# SCH_LaserTag-TTGO_2024-07-18.net
KiCad netlist of a schematic drawn in EasyEDA
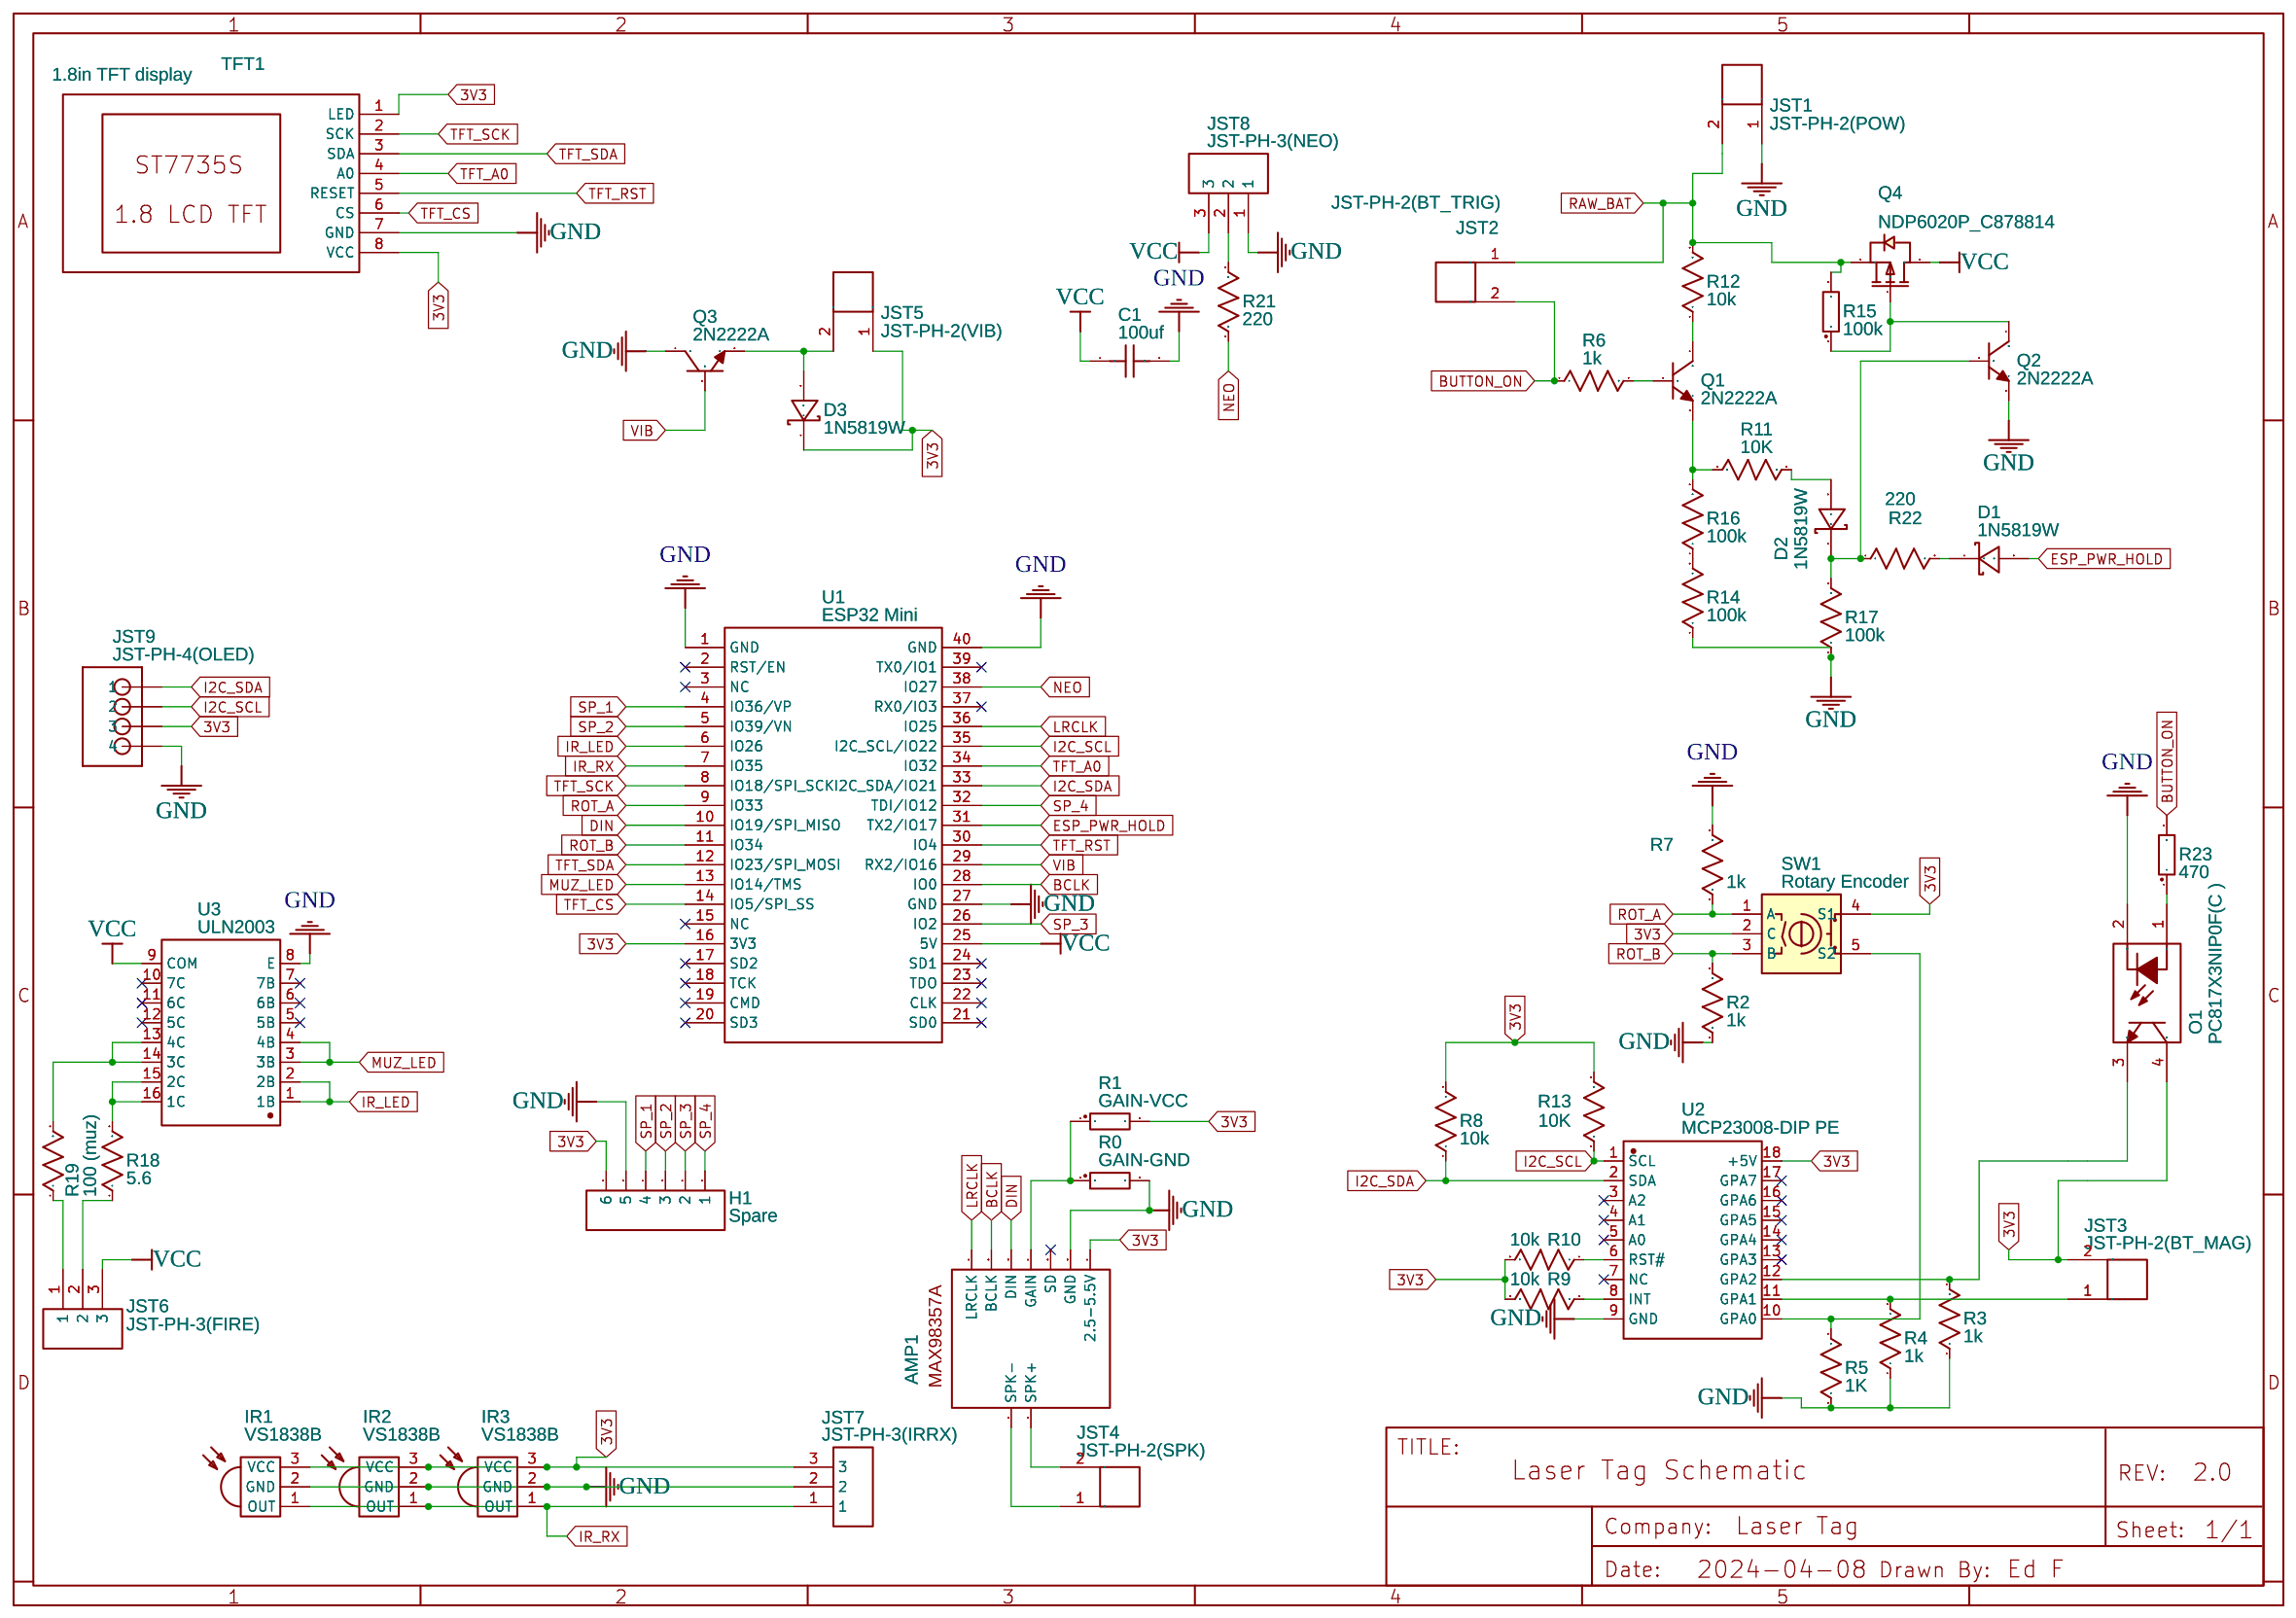
[diagram p0: schematic sheet]

(export (version "E")
  (design (tool "Eeschema 10.0.6"))
  (components
    (comp (ref "AMP1")
      (value "Amplifier")
      (fields (field (name "Manufacturer Part") "3006") (field (name "Manufacturer") "Adafruit"))
      (libsource (lib "") (part "I2S MAX98357A MODULE"))
    )
    (comp (ref "C1") (value "100uf") (libsource (lib "") (part "C_0603_US")))
    (comp (ref "D1")
      (value "1N5819W")
      (fields (field (name "Manufacturer") "Shandong Jingdao Microelectronics"))
      (libsource (lib "") (part "1N5819W_1"))
    )
    (comp (ref "D2")
      (value "1N5819W")
      (fields (field (name "Manufacturer") "Shandong Jingdao Microelectronics"))
      (libsource (lib "") (part "1N5819W"))
    )
    (comp (ref "D3")
      (value "1N5819W")
      (fields (field (name "Manufacturer") "Shandong Jingdao Microelectronics"))
      (libsource (lib "") (part "1N5819W"))
    )
    (comp (ref "H1") (value "Spare") (libsource (lib "") (part "HDR-F-2.54_1x6")))
    (comp (ref "IR1") (value "VS1838B") (libsource (lib "") (part "VS1838B")))
    (comp (ref "IR2") (value "VS1838B") (libsource (lib "") (part "VS1838B")))
    (comp (ref "IR3") (value "VS1838B") (libsource (lib "") (part "VS1838B")))
    (comp (ref "JST1")
      (value "JST-PH-2(POW)")
      (fields (field (name "Manufacturer Part") "JST PH 2 Pin"))
      (libsource (lib "") (part "JST PH 2 Pin_1"))
    )
    (comp (ref "JST2")
      (value "JST-PH-2(BT_TRIG)")
      (fields (field (name "Manufacturer Part") "JST PH 2 Pin"))
      (libsource (lib "") (part "JST PH 2 Pin"))
    )
    (comp (ref "JST3")
      (value "JST-PH-2(BT_MAG)")
      (fields (field (name "Manufacturer Part") "JST PH 2 Pin"))
      (libsource (lib "") (part "JST PH 2 Pin_2"))
    )
    (comp (ref "JST4")
      (value "JST-PH-2(SPK)")
      (fields (field (name "Manufacturer Part") "JST PH 2 Pin"))
      (libsource (lib "") (part "JST PH 2 Pin_2"))
    )
    (comp (ref "JST5")
      (value "JST-PH-2(VIB)")
      (fields (field (name "Manufacturer Part") "JST PH 2 Pin"))
      (libsource (lib "") (part "JST PH 2 Pin_1"))
    )
    (comp (ref "JST6")
      (value "JST-PH-3(FIRE)")
      (fields (field (name "Manufacturer Part") "JST PH 2-PIN 2.0MM TOP ENTRY"))
      (libsource (lib "") (part "JST PH 3-PIN 2.0MM TOP ENTRY_2"))
    )
    (comp (ref "JST7")
      (value "JST-PH-3(IRRX)")
      (fields (field (name "Manufacturer Part") "JST PH 2-PIN 2.0MM TOP ENTRY"))
      (libsource (lib "") (part "JST PH 3-PIN 2.0MM TOP ENTRY"))
    )
    (comp (ref "JST8")
      (value "JST-PH-3(NEO)")
      (fields (field (name "Manufacturer Part") "JST PH 2-PIN 2.0MM TOP ENTRY"))
      (libsource (lib "") (part "JST PH 3-PIN 2.0MM TOP ENTRY_1"))
    )
    (comp (ref "JST9") (value "JST-PH-4(OLED)") (libsource (lib "") (part "JST-PH-4-HEADER")))
    (comp (ref "O1")
      (value "PC817X3NIP0F(C )")
      (fields (field (name "Manufacturer Part") "PC817X3NIP0F") (field (name "Manufacturer") "SHARP(夏普)"))
      (libsource (lib "") (part "PC817X3NIP0F(C )"))
    )
    (comp (ref "Q1")
      (value "2N2222A")
      (fields (field (name "Manufacturer") "BLUE ROCKET(蓝箭)"))
      (libsource (lib "") (part "2N2222A_1"))
    )
    (comp (ref "Q2")
      (value "2N2222A")
      (fields (field (name "Manufacturer") "BLUE ROCKET(蓝箭)"))
      (libsource (lib "") (part "2N2222A_1"))
    )
    (comp (ref "Q3")
      (value "2N2222A")
      (fields (field (name "Manufacturer") "BLUE ROCKET(蓝箭)"))
      (libsource (lib "") (part "2N2222A"))
    )
    (comp (ref "Q4")
      (value "NDP6020P_C878814")
      (fields (field (name "Manufacturer Part") "NDP6020P-VB") (field (name "Manufacturer") "VBsemi(微碧半导体)"))
      (libsource (lib "") (part "NDP6020P_C878814"))
    )
    (comp (ref "R0") (value "GAIN-GND") (libsource (lib "") (part "PTH-RESISTOR-VERT-1W_1")))
    (comp (ref "R1") (value "GAIN-VCC") (libsource (lib "") (part "PTH-RESISTOR-VERT-1W_1")))
    (comp (ref "R2") (value "1k") (libsource (lib "") (part "R_0603_US")))
    (comp (ref "R3") (value "1k") (libsource (lib "") (part "R_0603_US")))
    (comp (ref "R4") (value "1k") (libsource (lib "") (part "R_0603_US")))
    (comp (ref "R5") (value "1K") (libsource (lib "") (part "R_0603_US")))
    (comp (ref "R6") (value "1k") (libsource (lib "") (part "R_0603_US_1")))
    (comp (ref "R7") (value "1k") (libsource (lib "") (part "R_0603_US")))
    (comp (ref "R8") (value "10k") (libsource (lib "") (part "R_0603_US")))
    (comp (ref "R9") (value "10k") (libsource (lib "") (part "R_0603_US_2")))
    (comp (ref "R10") (value "10k") (libsource (lib "") (part "R_0603_US_2")))
    (comp (ref "R11") (value "10K") (libsource (lib "") (part "R_0603_US_1")))
    (comp (ref "R12") (value "10k") (libsource (lib "") (part "R_0603_US")))
    (comp (ref "R13") (value "10K") (libsource (lib "") (part "R_0603_US")))
    (comp (ref "R14") (value "100k") (libsource (lib "") (part "R_0603_US")))
    (comp (ref "R15") (value "100k") (libsource (lib "") (part "PTH-RESISTOR-VERT-1W")))
    (comp (ref "R16") (value "100k") (libsource (lib "") (part "R_0603_US")))
    (comp (ref "R17") (value "100k") (libsource (lib "") (part "R_0603_US")))
    (comp (ref "R18") (value "5.6") (libsource (lib "") (part "R_0603_US")))
    (comp (ref "R19") (value "100 (muz)") (libsource (lib "") (part "R_0603_US")))
    (comp (ref "R21") (value "220") (libsource (lib "") (part "R_0603_US")))
    (comp (ref "R22") (value "220") (libsource (lib "") (part "R_0603_US_1")))
    (comp (ref "R23") (value "470") (libsource (lib "") (part "PTH-RESISTOR-VERT-1W")))
    (comp (ref "SW1") (value "Rotary Encoder") (libsource (lib "") (part "Rotary Encoder")))
    (comp (ref "TFT1")
      (value "1.8in TFT display")
      (libsource (lib "") (part "1.8inch LCD TFT ST7735S Waveshare"))
    )
    (comp (ref "U1") (value "ESP32 Mini") (libsource (lib "") (part "ESP32 Mini")))
    (comp (ref "U2")
      (value "MCP23008-DIP PE")
      (fields
        (field (name "Manufacturer Part") "MCP23008-E/P")
        (field (name "Manufacturer") "MICROCHIP(美国微芯)")
      )
      (libsource (lib "") (part "MCP23008-DIP PE"))
    )
    (comp (ref "U3")
      (value "ULN2003")
      (fields (field (name "Manufacturer Part") "ULN2003APG") (field (name "Manufacturer") "TOSHIBA"))
      (libsource (lib "") (part "ULN2003APG"))
    )
  )
  (nets
    (net (code "1") (name "3V3") (class "Default")
      (node (ref "AMP1") (pin "H7") (pinfunction "2.5-5.5V_H7") (pintype "unspecified"))
      (node (ref "D3") (pin "1") (pinfunction "1_1") (pintype "unspecified"))
      (node (ref "H1") (pin "6") (pinfunction "6_6") (pintype "input"))
      (node (ref "IR1") (pin "3") (pinfunction "VCC_3") (pintype "bidirectional"))
      (node (ref "IR2") (pin "3") (pinfunction "VCC_3") (pintype "bidirectional"))
      (node (ref "IR3") (pin "3") (pinfunction "VCC_3") (pintype "bidirectional"))
      (node (ref "JST3") (pin "2") (pinfunction "2_2") (pintype "unspecified"))
      (node (ref "JST5") (pin "1") (pinfunction "1_1") (pintype "unspecified"))
      (node (ref "JST7") (pin "3") (pinfunction "3_3") (pintype "unspecified"))
      (node (ref "JST9") (pin "3") (pinfunction "3_3") (pintype "unspecified"))
      (node (ref "O1") (pin "4") (pinfunction "COL_4") (pintype "unspecified"))
      (node (ref "R1") (pin "2") (pinfunction "2_2") (pintype "input"))
      (node (ref "R10") (pin "2") (pinfunction "2_2") (pintype "unspecified"))
      (node (ref "R13") (pin "2") (pinfunction "2_2") (pintype "unspecified"))
      (node (ref "R8") (pin "2") (pinfunction "2_2") (pintype "unspecified"))
      (node (ref "R9") (pin "2") (pinfunction "2_2") (pintype "unspecified"))
      (node (ref "SW1") (pin "2") (pinfunction "C_2") (pintype "unspecified"))
      (node (ref "SW1") (pin "4") (pinfunction "S1_4") (pintype "unspecified"))
      (node (ref "TFT1") (pin "1") (pinfunction "LED_1") (pintype "unspecified"))
      (node (ref "TFT1") (pin "8") (pinfunction "VCC_8") (pintype "unspecified"))
      (node (ref "U1") (pin "16") (pinfunction "3V3_16") (pintype "unspecified"))
      (node (ref "U2") (pin "18") (pinfunction "+5V_18") (pintype "unspecified"))
    )
    (net (code "2") (name "BCLK") (class "Default")
      (node (ref "AMP1") (pin "H2") (pinfunction "BCLK_H2") (pintype "unspecified"))
      (node (ref "U1") (pin "28") (pinfunction "IO0_28") (pintype "unspecified"))
    )
    (net (code "3") (name "BUTTON_ON") (class "Default")
      (node (ref "JST2") (pin "2") (pinfunction "2_2") (pintype "unspecified"))
      (node (ref "R23") (pin "2") (pinfunction "2_2") (pintype "input"))
      (node (ref "R6") (pin "1") (pinfunction "1_1") (pintype "unspecified"))
    )
    (net (code "4") (name "DIN") (class "Default")
      (node (ref "AMP1") (pin "H3") (pinfunction "DIN_H3") (pintype "unspecified"))
      (node (ref "U1") (pin "10") (pinfunction "IO19/SPI_MISO_10") (pintype "unspecified"))
    )
    (net (code "5") (name "ESP_PWR_HOLD") (class "Default")
      (node (ref "D1") (pin "2") (pinfunction "2_2") (pintype "unspecified"))
      (node (ref "U1") (pin "31") (pinfunction "TX2/IO17_31") (pintype "unspecified"))
    )
    (net (code "6") (name "GND") (class "Default")
      (node (ref "AMP1") (pin "H6") (pinfunction "GND_H6") (pintype "unspecified"))
      (node (ref "C1") (pin "2") (pinfunction "2_2") (pintype "unspecified"))
      (node (ref "H1") (pin "5") (pinfunction "5_5") (pintype "input"))
      (node (ref "IR1") (pin "2") (pinfunction "GND_2") (pintype "bidirectional"))
      (node (ref "IR2") (pin "2") (pinfunction "GND_2") (pintype "bidirectional"))
      (node (ref "IR3") (pin "2") (pinfunction "GND_2") (pintype "bidirectional"))
      (node (ref "JST1") (pin "1") (pinfunction "1_1") (pintype "unspecified"))
      (node (ref "JST7") (pin "2") (pinfunction "2_2") (pintype "unspecified"))
      (node (ref "JST8") (pin "1") (pinfunction "1_1") (pintype "unspecified"))
      (node (ref "JST9") (pin "4") (pinfunction "4_4") (pintype "unspecified"))
      (node (ref "O1") (pin "2") (pinfunction "CAT_2") (pintype "unspecified"))
      (node (ref "Q2") (pin "3") (pinfunction "E_3") (pintype "unspecified"))
      (node (ref "Q3") (pin "1") (pinfunction "C_1") (pintype "unspecified"))
      (node (ref "R0") (pin "2") (pinfunction "2_2") (pintype "input"))
      (node (ref "R14") (pin "1") (pinfunction "1_1") (pintype "unspecified"))
      (node (ref "R17") (pin "1") (pinfunction "1_1") (pintype "unspecified"))
      (node (ref "R2") (pin "1") (pinfunction "1_1") (pintype "unspecified"))
      (node (ref "R3") (pin "1") (pinfunction "1_1") (pintype "unspecified"))
      (node (ref "R4") (pin "1") (pinfunction "1_1") (pintype "unspecified"))
      (node (ref "R5") (pin "1") (pinfunction "1_1") (pintype "unspecified"))
      (node (ref "R7") (pin "2") (pinfunction "2_2") (pintype "unspecified"))
      (node (ref "TFT1") (pin "7") (pinfunction "GND_7") (pintype "unspecified"))
      (node (ref "U1") (pin "1") (pinfunction "GND_1") (pintype "unspecified"))
      (node (ref "U1") (pin "27") (pinfunction "GND_27") (pintype "unspecified"))
      (node (ref "U1") (pin "40") (pinfunction "GND_40") (pintype "unspecified"))
      (node (ref "U2") (pin "9") (pinfunction "GND_9") (pintype "unspecified"))
      (node (ref "U3") (pin "8") (pinfunction "E_8") (pintype "unspecified"))
    )
    (net (code "7") (name "I2C_SCL") (class "Default")
      (node (ref "JST9") (pin "2") (pinfunction "2_2") (pintype "unspecified"))
      (node (ref "R13") (pin "1") (pinfunction "1_1") (pintype "unspecified"))
      (node (ref "U1") (pin "35") (pinfunction "I2C_SCL/IO22_35") (pintype "unspecified"))
      (node (ref "U2") (pin "1") (pinfunction "SCL_1") (pintype "unspecified"))
    )
    (net (code "8") (name "I2C_SDA") (class "Default")
      (node (ref "JST9") (pin "1") (pinfunction "1_1") (pintype "unspecified"))
      (node (ref "R8") (pin "1") (pinfunction "1_1") (pintype "unspecified"))
      (node (ref "U1") (pin "33") (pinfunction "I2C_SDA/IO21_33") (pintype "unspecified"))
      (node (ref "U2") (pin "2") (pinfunction "SDA_2") (pintype "unspecified"))
    )
    (net (code "9") (name "IR_LED") (class "Default")
      (node (ref "U1") (pin "6") (pinfunction "IO26_6") (pintype "unspecified"))
      (node (ref "U3") (pin "1") (pinfunction "1B_1") (pintype "unspecified"))
      (node (ref "U3") (pin "2") (pinfunction "2B_2") (pintype "unspecified"))
    )
    (net (code "10") (name "IR_RX") (class "Default")
      (node (ref "IR1") (pin "1") (pinfunction "OUT_1") (pintype "bidirectional"))
      (node (ref "IR2") (pin "1") (pinfunction "OUT_1") (pintype "bidirectional"))
      (node (ref "IR3") (pin "1") (pinfunction "OUT_1") (pintype "bidirectional"))
      (node (ref "JST7") (pin "1") (pinfunction "1_1") (pintype "unspecified"))
      (node (ref "U1") (pin "7") (pinfunction "IO35_7") (pintype "unspecified"))
    )
    (net (code "11") (name "LRCLK") (class "Default")
      (node (ref "AMP1") (pin "H1") (pinfunction "LRCLK_H1") (pintype "unspecified"))
      (node (ref "U1") (pin "36") (pinfunction "IO25_36") (pintype "unspecified"))
    )
    (net (code "12") (name "MUZ_LED") (class "Default")
      (node (ref "U1") (pin "13") (pinfunction "IO14/TMS_13") (pintype "unspecified"))
      (node (ref "U3") (pin "3") (pinfunction "3B_3") (pintype "unspecified"))
      (node (ref "U3") (pin "4") (pinfunction "4B_4") (pintype "unspecified"))
    )
    (net (code "13") (name "NEO") (class "Default")
      (node (ref "R21") (pin "1") (pinfunction "1_1") (pintype "unspecified"))
      (node (ref "U1") (pin "38") (pinfunction "IO27_38") (pintype "unspecified"))
    )
    (net (code "14") (name "Net-(AMP1-GAIN)") (class "Default")
      (node (ref "AMP1") (pin "H4") (pinfunction "GAIN_H4") (pintype "unspecified"))
      (node (ref "R0") (pin "1") (pinfunction "1_1") (pintype "input"))
      (node (ref "R1") (pin "1") (pinfunction "1_1") (pintype "input"))
    )
    (net (code "15") (name "Net-(AMP1-SPK+)") (class "Default")
      (node (ref "AMP1") (pin "H9") (pinfunction "SPK+_H9") (pintype "unspecified"))
      (node (ref "JST4") (pin "2") (pinfunction "2_2") (pintype "unspecified"))
    )
    (net (code "16") (name "Net-(AMP1-SPK-)") (class "Default")
      (node (ref "AMP1") (pin "H8") (pinfunction "SPK-_H8") (pintype "unspecified"))
      (node (ref "JST4") (pin "1") (pinfunction "1_1") (pintype "unspecified"))
    )
    (net (code "17") (name "Net-(D1-Pad1)") (class "Default")
      (node (ref "D1") (pin "1") (pinfunction "1_1") (pintype "unspecified"))
      (node (ref "R22") (pin "2") (pinfunction "2_2") (pintype "unspecified"))
    )
    (net (code "18") (name "Net-(D2-Pad2)") (class "Default")
      (node (ref "D2") (pin "2") (pinfunction "2_2") (pintype "unspecified"))
      (node (ref "R11") (pin "2") (pinfunction "2_2") (pintype "unspecified"))
    )
    (net (code "19") (name "Net-(JST6-Pad1)") (class "Default")
      (node (ref "JST6") (pin "1") (pinfunction "1_1") (pintype "unspecified"))
      (node (ref "R19") (pin "1") (pinfunction "1_1") (pintype "unspecified"))
    )
    (net (code "20") (name "Net-(JST6-Pad2)") (class "Default")
      (node (ref "JST6") (pin "2") (pinfunction "2_2") (pintype "unspecified"))
      (node (ref "R18") (pin "1") (pinfunction "1_1") (pintype "unspecified"))
    )
    (net (code "21") (name "Net-(JST8-Pad2)") (class "Default")
      (node (ref "JST8") (pin "2") (pinfunction "2_2") (pintype "unspecified"))
      (node (ref "R21") (pin "2") (pinfunction "2_2") (pintype "unspecified"))
    )
    (net (code "22") (name "Net-(O1-AN)") (class "Default")
      (node (ref "O1") (pin "1") (pinfunction "AN_1") (pintype "unspecified"))
      (node (ref "R23") (pin "1") (pinfunction "1_1") (pintype "input"))
    )
    (net (code "23") (name "Net-(O1-EM)") (class "Default")
      (node (ref "O1") (pin "3") (pinfunction "EM_3") (pintype "unspecified"))
      (node (ref "R3") (pin "2") (pinfunction "2_2") (pintype "unspecified"))
      (node (ref "U2") (pin "12") (pinfunction "GPA2_12") (pintype "unspecified"))
    )
    (net (code "24") (name "Net-(Q1-B)") (class "Default")
      (node (ref "Q1") (pin "2") (pinfunction "B_2") (pintype "unspecified"))
      (node (ref "R6") (pin "2") (pinfunction "2_2") (pintype "unspecified"))
    )
    (net (code "25") (name "Net-(Q1-C)") (class "Default")
      (node (ref "Q1") (pin "1") (pinfunction "C_1") (pintype "unspecified"))
      (node (ref "R12") (pin "1") (pinfunction "1_1") (pintype "unspecified"))
    )
    (net (code "26") (name "Net-(Q1-E)") (class "Default")
      (node (ref "Q1") (pin "3") (pinfunction "E_3") (pintype "unspecified"))
      (node (ref "R11") (pin "1") (pinfunction "1_1") (pintype "unspecified"))
      (node (ref "R16") (pin "2") (pinfunction "2_2") (pintype "unspecified"))
    )
    (net (code "27") (name "Net-(Q2-B)") (class "Default")
      (node (ref "D2") (pin "1") (pinfunction "1_1") (pintype "unspecified"))
      (node (ref "Q2") (pin "2") (pinfunction "B_2") (pintype "unspecified"))
      (node (ref "R17") (pin "2") (pinfunction "2_2") (pintype "unspecified"))
      (node (ref "R22") (pin "1") (pinfunction "1_1") (pintype "unspecified"))
    )
    (net (code "28") (name "Net-(Q2-C)") (class "Default")
      (node (ref "Q2") (pin "1") (pinfunction "C_1") (pintype "unspecified"))
      (node (ref "Q4") (pin "1") (pinfunction "G_1") (pintype "unspecified"))
      (node (ref "R15") (pin "1") (pinfunction "1_1") (pintype "input"))
    )
    (net (code "29") (name "Net-(Q3-E)") (class "Default")
      (node (ref "D3") (pin "2") (pinfunction "2_2") (pintype "unspecified"))
      (node (ref "JST5") (pin "2") (pinfunction "2_2") (pintype "unspecified"))
      (node (ref "Q3") (pin "3") (pinfunction "E_3") (pintype "unspecified"))
    )
    (net (code "30") (name "Net-(R14-Pad2)") (class "Default")
      (node (ref "R14") (pin "2") (pinfunction "2_2") (pintype "unspecified"))
      (node (ref "R16") (pin "1") (pinfunction "1_1") (pintype "unspecified"))
    )
    (net (code "31") (name "Net-(SW1-S2)") (class "Default")
      (node (ref "R5") (pin "2") (pinfunction "2_2") (pintype "unspecified"))
      (node (ref "SW1") (pin "5") (pinfunction "S2_5") (pintype "unspecified"))
      (node (ref "U2") (pin "10") (pinfunction "GPA0_10") (pintype "unspecified"))
    )
    (net (code "32") (name "Net-(U2-GPA1)") (class "Default")
      (node (ref "JST3") (pin "1") (pinfunction "1_1") (pintype "unspecified"))
      (node (ref "R4") (pin "2") (pinfunction "2_2") (pintype "unspecified"))
      (node (ref "U2") (pin "11") (pinfunction "GPA1_11") (pintype "unspecified"))
    )
    (net (code "33") (name "Net-(U2-INT)") (class "Default")
      (node (ref "R9") (pin "1") (pinfunction "1_1") (pintype "unspecified"))
      (node (ref "U2") (pin "8") (pinfunction "INT_8") (pintype "unspecified"))
    )
    (net (code "34") (name "Net-(U2-RST#)") (class "Default")
      (node (ref "R10") (pin "1") (pinfunction "1_1") (pintype "unspecified"))
      (node (ref "U2") (pin "6") (pinfunction "RST#_6") (pintype "unspecified"))
    )
    (net (code "35") (name "Net-(U3-1C)") (class "Default")
      (node (ref "R18") (pin "2") (pinfunction "2_2") (pintype "unspecified"))
      (node (ref "U3") (pin "15") (pinfunction "2C_15") (pintype "unspecified"))
      (node (ref "U3") (pin "16") (pinfunction "1C_16") (pintype "unspecified"))
    )
    (net (code "36") (name "Net-(U3-3C)") (class "Default")
      (node (ref "R19") (pin "2") (pinfunction "2_2") (pintype "unspecified"))
      (node (ref "U3") (pin "13") (pinfunction "4C_13") (pintype "unspecified"))
      (node (ref "U3") (pin "14") (pinfunction "3C_14") (pintype "unspecified"))
    )
    (net (code "37") (name "RAW_BAT") (class "Default")
      (node (ref "JST1") (pin "2") (pinfunction "2_2") (pintype "unspecified"))
      (node (ref "JST2") (pin "1") (pinfunction "1_1") (pintype "unspecified"))
      (node (ref "Q4") (pin "3") (pinfunction "S_3") (pintype "unspecified"))
      (node (ref "R12") (pin "2") (pinfunction "2_2") (pintype "unspecified"))
      (node (ref "R15") (pin "2") (pinfunction "2_2") (pintype "input"))
    )
    (net (code "38") (name "ROT_A") (class "Default")
      (node (ref "R7") (pin "1") (pinfunction "1_1") (pintype "unspecified"))
      (node (ref "SW1") (pin "1") (pinfunction "A_1") (pintype "unspecified"))
      (node (ref "U1") (pin "9") (pinfunction "IO33_9") (pintype "unspecified"))
    )
    (net (code "39") (name "ROT_B") (class "Default")
      (node (ref "R2") (pin "2") (pinfunction "2_2") (pintype "unspecified"))
      (node (ref "SW1") (pin "3") (pinfunction "B_3") (pintype "unspecified"))
      (node (ref "U1") (pin "11") (pinfunction "IO34_11") (pintype "unspecified"))
    )
    (net (code "40") (name "SP_1") (class "Default")
      (node (ref "H1") (pin "4") (pinfunction "4_4") (pintype "input"))
      (node (ref "U1") (pin "4") (pinfunction "IO36/VP_4") (pintype "unspecified"))
    )
    (net (code "41") (name "SP_2") (class "Default")
      (node (ref "H1") (pin "3") (pinfunction "3_3") (pintype "input"))
      (node (ref "U1") (pin "5") (pinfunction "IO39/VN_5") (pintype "unspecified"))
    )
    (net (code "42") (name "SP_3") (class "Default")
      (node (ref "H1") (pin "2") (pinfunction "2_2") (pintype "input"))
      (node (ref "U1") (pin "26") (pinfunction "IO2_26") (pintype "unspecified"))
    )
    (net (code "43") (name "SP_4") (class "Default")
      (node (ref "H1") (pin "1") (pinfunction "1_1") (pintype "input"))
      (node (ref "U1") (pin "32") (pinfunction "TDI/IO12_32") (pintype "unspecified"))
    )
    (net (code "44") (name "TFT_A0") (class "Default")
      (node (ref "TFT1") (pin "4") (pinfunction "A0_4") (pintype "unspecified"))
      (node (ref "U1") (pin "34") (pinfunction "IO32_34") (pintype "unspecified"))
    )
    (net (code "45") (name "TFT_CS") (class "Default")
      (node (ref "TFT1") (pin "6") (pinfunction "CS_6") (pintype "unspecified"))
      (node (ref "U1") (pin "14") (pinfunction "IO5/SPI_SS_14") (pintype "unspecified"))
    )
    (net (code "46") (name "TFT_RST") (class "Default")
      (node (ref "TFT1") (pin "5") (pinfunction "RESET_5") (pintype "unspecified"))
      (node (ref "U1") (pin "30") (pinfunction "IO4_30") (pintype "unspecified"))
    )
    (net (code "47") (name "TFT_SCK") (class "Default")
      (node (ref "TFT1") (pin "2") (pinfunction "SCK_2") (pintype "unspecified"))
      (node (ref "U1") (pin "8") (pinfunction "IO18/SPI_SCK_8") (pintype "unspecified"))
    )
    (net (code "48") (name "TFT_SDA") (class "Default")
      (node (ref "TFT1") (pin "3") (pinfunction "SDA_3") (pintype "unspecified"))
      (node (ref "U1") (pin "12") (pinfunction "IO23/SPI_MOSI_12") (pintype "unspecified"))
    )
    (net (code "49") (name "VCC") (class "Default")
      (node (ref "C1") (pin "1") (pinfunction "1_1") (pintype "unspecified"))
      (node (ref "JST6") (pin "3") (pinfunction "3_3") (pintype "unspecified"))
      (node (ref "JST8") (pin "3") (pinfunction "3_3") (pintype "unspecified"))
      (node (ref "Q4") (pin "2") (pinfunction "D_2") (pintype "unspecified"))
      (node (ref "U1") (pin "25") (pinfunction "5V_25") (pintype "unspecified"))
      (node (ref "U3") (pin "9") (pinfunction "COM_9") (pintype "unspecified"))
    )
    (net (code "50") (name "VIB") (class "Default")
      (node (ref "Q3") (pin "2") (pinfunction "B_2") (pintype "unspecified"))
      (node (ref "U1") (pin "29") (pinfunction "RX2/IO16_29") (pintype "unspecified"))
    )
    (net (code "51") (name "unconnected-(AMP1-SD-PadH5)") (class "Default")
      (node (ref "AMP1") (pin "H5") (pinfunction "SD_H5") (pintype "unspecified+no_connect"))
    )
    (net (code "52") (name "unconnected-(U1-CLK-Pad22)") (class "Default")
      (node (ref "U1") (pin "22") (pinfunction "CLK_22") (pintype "unspecified+no_connect"))
    )
    (net (code "53") (name "unconnected-(U1-CMD-Pad19)") (class "Default")
      (node (ref "U1") (pin "19") (pinfunction "CMD_19") (pintype "unspecified+no_connect"))
    )
    (net (code "54") (name "unconnected-(U1-NC-Pad3)") (class "Default")
      (node (ref "U1") (pin "3") (pinfunction "NC_3") (pintype "unspecified+no_connect"))
    )
    (net (code "55") (name "unconnected-(U1-NC-Pad15)") (class "Default")
      (node (ref "U1") (pin "15") (pinfunction "NC_15") (pintype "unspecified+no_connect"))
    )
    (net (code "56") (name "unconnected-(U1-RST{slash}EN-Pad2)") (class "Default")
      (node (ref "U1") (pin "2") (pinfunction "RST/EN_2") (pintype "unspecified+no_connect"))
    )
    (net (code "57") (name "unconnected-(U1-RX0{slash}IO3-Pad37)") (class "Default")
      (node (ref "U1") (pin "37") (pinfunction "RX0/IO3_37") (pintype "unspecified+no_connect"))
    )
    (net (code "58") (name "unconnected-(U1-SD0-Pad21)") (class "Default")
      (node (ref "U1") (pin "21") (pinfunction "SD0_21") (pintype "unspecified+no_connect"))
    )
    (net (code "59") (name "unconnected-(U1-SD1-Pad24)") (class "Default")
      (node (ref "U1") (pin "24") (pinfunction "SD1_24") (pintype "unspecified+no_connect"))
    )
    (net (code "60") (name "unconnected-(U1-SD2-Pad17)") (class "Default")
      (node (ref "U1") (pin "17") (pinfunction "SD2_17") (pintype "unspecified+no_connect"))
    )
    (net (code "61") (name "unconnected-(U1-SD3-Pad20)") (class "Default")
      (node (ref "U1") (pin "20") (pinfunction "SD3_20") (pintype "unspecified+no_connect"))
    )
    (net (code "62") (name "unconnected-(U1-TCK-Pad18)") (class "Default")
      (node (ref "U1") (pin "18") (pinfunction "TCK_18") (pintype "unspecified+no_connect"))
    )
    (net (code "63") (name "unconnected-(U1-TDO-Pad23)") (class "Default")
      (node (ref "U1") (pin "23") (pinfunction "TDO_23") (pintype "unspecified+no_connect"))
    )
    (net (code "64") (name "unconnected-(U1-TX0{slash}IO1-Pad39)") (class "Default")
      (node (ref "U1") (pin "39") (pinfunction "TX0/IO1_39") (pintype "unspecified+no_connect"))
    )
    (net (code "65") (name "unconnected-(U2-A0-Pad5)") (class "Default")
      (node (ref "U2") (pin "5") (pinfunction "A0_5") (pintype "unspecified+no_connect"))
    )
    (net (code "66") (name "unconnected-(U2-A1-Pad4)") (class "Default")
      (node (ref "U2") (pin "4") (pinfunction "A1_4") (pintype "unspecified+no_connect"))
    )
    (net (code "67") (name "unconnected-(U2-A2-Pad3)") (class "Default")
      (node (ref "U2") (pin "3") (pinfunction "A2_3") (pintype "unspecified+no_connect"))
    )
    (net (code "68") (name "unconnected-(U2-GPA3-Pad13)") (class "Default")
      (node (ref "U2") (pin "13") (pinfunction "GPA3_13") (pintype "unspecified+no_connect"))
    )
    (net (code "69") (name "unconnected-(U2-GPA4-Pad14)") (class "Default")
      (node (ref "U2") (pin "14") (pinfunction "GPA4_14") (pintype "unspecified+no_connect"))
    )
    (net (code "70") (name "unconnected-(U2-GPA5-Pad15)") (class "Default")
      (node (ref "U2") (pin "15") (pinfunction "GPA5_15") (pintype "unspecified+no_connect"))
    )
    (net (code "71") (name "unconnected-(U2-GPA6-Pad16)") (class "Default")
      (node (ref "U2") (pin "16") (pinfunction "GPA6_16") (pintype "unspecified+no_connect"))
    )
    (net (code "72") (name "unconnected-(U2-GPA7-Pad17)") (class "Default")
      (node (ref "U2") (pin "17") (pinfunction "GPA7_17") (pintype "unspecified+no_connect"))
    )
    (net (code "73") (name "unconnected-(U2-NC-Pad7)") (class "Default")
      (node (ref "U2") (pin "7") (pinfunction "NC_7") (pintype "unspecified+no_connect"))
    )
    (net (code "74") (name "unconnected-(U3-5B-Pad5)") (class "Default")
      (node (ref "U3") (pin "5") (pinfunction "5B_5") (pintype "unspecified+no_connect"))
    )
    (net (code "75") (name "unconnected-(U3-5C-Pad12)") (class "Default")
      (node (ref "U3") (pin "12") (pinfunction "5C_12") (pintype "unspecified+no_connect"))
    )
    (net (code "76") (name "unconnected-(U3-6B-Pad6)") (class "Default")
      (node (ref "U3") (pin "6") (pinfunction "6B_6") (pintype "unspecified+no_connect"))
    )
    (net (code "77") (name "unconnected-(U3-6C-Pad11)") (class "Default")
      (node (ref "U3") (pin "11") (pinfunction "6C_11") (pintype "unspecified+no_connect"))
    )
    (net (code "78") (name "unconnected-(U3-7B-Pad7)") (class "Default")
      (node (ref "U3") (pin "7") (pinfunction "7B_7") (pintype "unspecified+no_connect"))
    )
    (net (code "79") (name "unconnected-(U3-7C-Pad10)") (class "Default")
      (node (ref "U3") (pin "10") (pinfunction "7C_10") (pintype "unspecified+no_connect"))
    )
  )
)
